# SparkFun_tDof-TMF8821_HQ.net
KiCad netlist of a schematic drawn in EAGLE
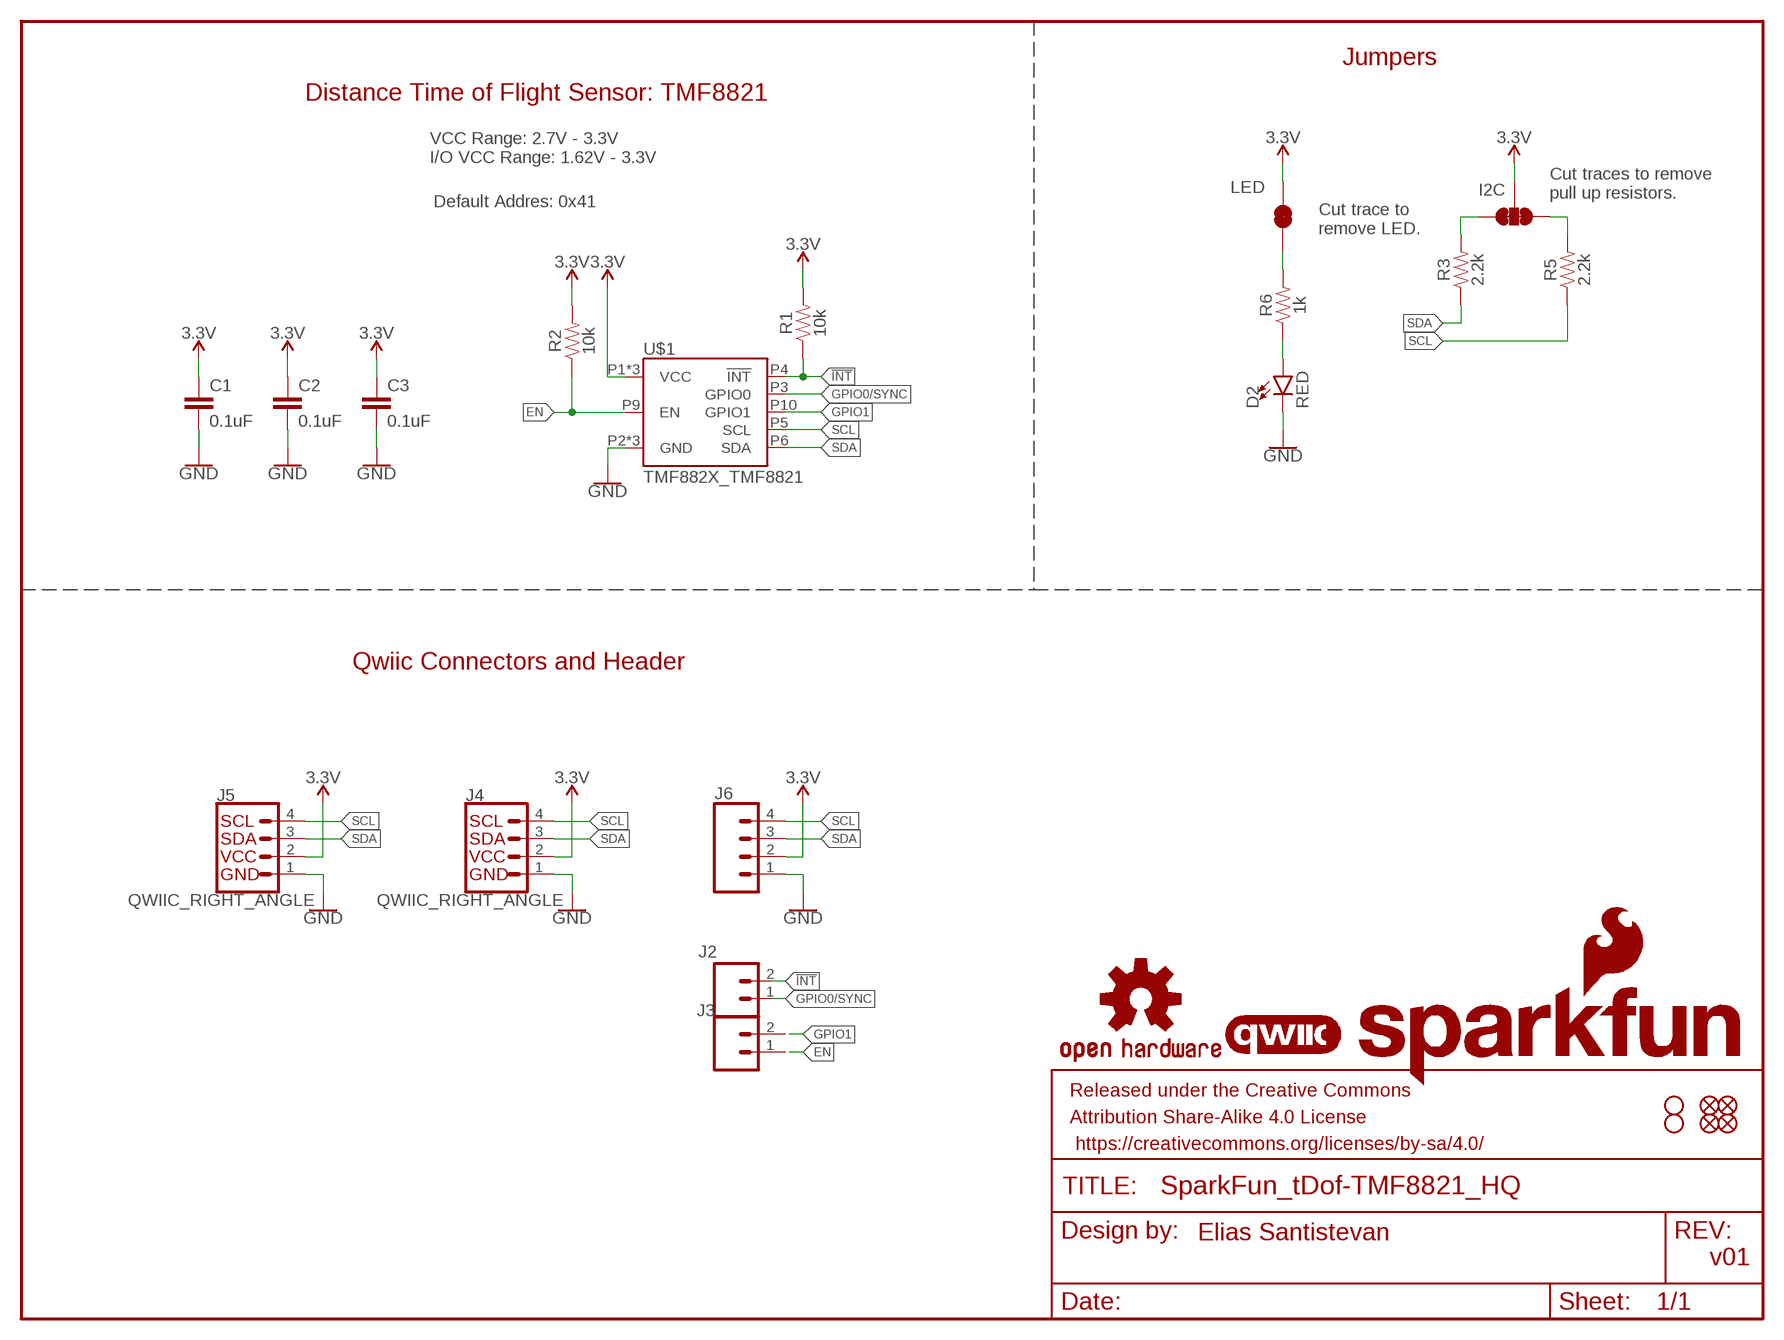
[diagram p0: schematic, sheet 1]

(export (version "E")
  (design (tool "Eeschema 10.0.6"))
  (components
    (comp (ref "C1")
      (value "0.1uF")
      (footprint "eagle-import:0402-TIGHT")
      (libsource (lib "eagle-import") (part "0.1UF-0402T-6.3V-10%-X7R"))
    )
    (comp (ref "C2")
      (value "0.1uF")
      (footprint "eagle-import:0402-TIGHT")
      (libsource (lib "eagle-import") (part "0.1UF-0402T-6.3V-10%-X7R"))
    )
    (comp (ref "C3")
      (value "0.1uF")
      (footprint "eagle-import:0402-TIGHT")
      (libsource (lib "eagle-import") (part "0.1UF-0402T-6.3V-10%-X7R"))
    )
    (comp (ref "D2")
      (value "RED")
      (footprint "eagle-import:LED-0603")
      (libsource (lib "eagle-import") (part "LED-RED0603"))
    )
    (comp (ref "FD5")
      (value "FIDUCIALUFIDUCIAL")
      (footprint "eagle-import:FIDUCIAL-MICRO")
      (libsource (lib "eagle-import") (part "FIDUCIALUFIDUCIAL"))
    )
    (comp (ref "FD6")
      (value "FIDUCIALUFIDUCIAL")
      (footprint "eagle-import:FIDUCIAL-MICRO")
      (libsource (lib "eagle-import") (part "FIDUCIALUFIDUCIAL"))
    )
    (comp (ref "FD7")
      (value "FIDUCIALUFIDUCIAL")
      (footprint "eagle-import:FIDUCIAL-MICRO")
      (libsource (lib "eagle-import") (part "FIDUCIALUFIDUCIAL"))
    )
    (comp (ref "FD8")
      (value "FIDUCIALUFIDUCIAL")
      (footprint "eagle-import:FIDUCIAL-MICRO")
      (libsource (lib "eagle-import") (part "FIDUCIALUFIDUCIAL"))
    )
    (comp (ref "FRAME2")
      (value "FRAME-LETTER")
      (footprint "eagle-import:CREATIVE_COMMONS")
      (libsource (lib "eagle-import") (part "FRAME-LETTER"))
    )
    (comp (ref "H7")
      (value "STAND-OFFTIGHT")
      (footprint "eagle-import:STAND-OFF-TIGHT")
      (libsource (lib "eagle-import") (part "STAND-OFFTIGHT"))
    )
    (comp (ref "H8")
      (value "STAND-OFFTIGHT")
      (footprint "eagle-import:STAND-OFF-TIGHT")
      (libsource (lib "eagle-import") (part "STAND-OFFTIGHT"))
    )
    (comp (ref "I2C")
      (value "I2C_PU")
      (footprint "eagle-import:SMT-JUMPER_3_2-NC_TRACE_SILK")
      (libsource (lib "eagle-import") (part "JUMPER-SMT_3_2-NC_TRACE_SILK"))
    )
    (comp (ref "J2")
      (value "CONN_021X02_NO_SILK")
      (footprint "eagle-import:1X02_NO_SILK")
      (libsource (lib "eagle-import") (part "CONN_021X02_NO_SILK"))
    )
    (comp (ref "J3")
      (value "CONN_021X02_NO_SILK")
      (footprint "eagle-import:1X02_NO_SILK")
      (libsource (lib "eagle-import") (part "CONN_021X02_NO_SILK"))
    )
    (comp (ref "J4")
      (value "QWIIC_RIGHT_ANGLE")
      (footprint "eagle-import:JST04_1MM_RA")
      (libsource (lib "eagle-import") (part "QWIIC_CONNECTORJS-1MM"))
    )
    (comp (ref "J5")
      (value "QWIIC_RIGHT_ANGLE")
      (footprint "eagle-import:JST04_1MM_RA")
      (libsource (lib "eagle-import") (part "QWIIC_CONNECTORJS-1MM"))
    )
    (comp (ref "J6")
      (value "CONN_041X04_NO_SILK")
      (footprint "eagle-import:1X04_NO_SILK")
      (libsource (lib "eagle-import") (part "CONN_041X04_NO_SILK"))
    )
    (comp (ref "LED")
      (value "LED")
      (footprint "eagle-import:SMT-JUMPER_2_NC_TRACE_SILK")
      (libsource (lib "eagle-import") (part "JUMPER-SMT_2_NC_TRACE_SILK"))
    )
    (comp (ref "LOGO1")
      (value "SFE_LOGO_NAME_FLAMEBLANK")
      (footprint "eagle-import:BLANK")
      (libsource (lib "eagle-import") (part "SFE_LOGO_NAME_FLAMEBLANK"))
    )
    (comp (ref "LOGO2")
      (value "QWIIC_LOGO_3MM")
      (footprint "eagle-import:QWIIC_3MM")
      (libsource (lib "eagle-import") (part "QWIIC_LOGO_3MM"))
    )
    (comp (ref "LOGO3")
      (value "OSHW-LOGONO_SILK")
      (footprint "eagle-import:DUMMY")
      (libsource (lib "eagle-import") (part "OSHW-LOGONO_SILK"))
    )
    (comp (ref "R1")
      (value "10k")
      (footprint "eagle-import:0402-TIGHT")
      (libsource (lib "eagle-import") (part "10KOHM-0402T-1/16W-1%"))
    )
    (comp (ref "R2")
      (value "10k")
      (footprint "eagle-import:0402-TIGHT")
      (libsource (lib "eagle-import") (part "10KOHM-0402T-1/16W-1%"))
    )
    (comp (ref "R3")
      (value "2.2k")
      (footprint "eagle-import:0402-TIGHT")
      (libsource (lib "eagle-import") (part "2.2KOHM-0402T-1/16W-1%"))
    )
    (comp (ref "R5")
      (value "2.2k")
      (footprint "eagle-import:0402-TIGHT")
      (libsource (lib "eagle-import") (part "2.2KOHM-0402T-1/16W-1%"))
    )
    (comp (ref "R6")
      (value "1k")
      (footprint "eagle-import:0402-TIGHT")
      (libsource (lib "eagle-import") (part "1KOHM-0402T-1/16W-1%"))
    )
    (comp (ref "U$1")
      (value "TMF882X_TMF8821")
      (footprint "eagle-import:TMF882X")
      (libsource (lib "eagle-import") (part "TMF882X_TMF8821"))
    )
  )
  (nets
    (net (code "1") (name "/~{INT}") (class "Default")
      (node (ref "J2") (pin "2") (pinfunction "2_2") (pintype "passive"))
      (node (ref "R1") (pin "1") (pinfunction "1_1") (pintype "passive"))
      (node (ref "U$1") (pin "P4") (pinfunction "~{INT}_P4") (pintype "bidirectional"))
    )
    (net (code "2") (name "3.3V") (class "Default")
      (node (ref "C1") (pin "1") (pinfunction "1_1") (pintype "passive"))
      (node (ref "C2") (pin "1") (pinfunction "1_1") (pintype "passive"))
      (node (ref "C3") (pin "1") (pinfunction "1_1") (pintype "passive"))
      (node (ref "I2C") (pin "2") (pinfunction "2_2") (pintype "passive"))
      (node (ref "J4") (pin "2") (pinfunction "2_2") (pintype "power_in"))
      (node (ref "J5") (pin "2") (pinfunction "2_2") (pintype "power_in"))
      (node (ref "J6") (pin "2") (pinfunction "2_2") (pintype "passive"))
      (node (ref "LED") (pin "2") (pinfunction "2_2") (pintype "passive"))
      (node (ref "R1") (pin "2") (pinfunction "2_2") (pintype "passive"))
      (node (ref "R2") (pin "2") (pinfunction "2_2") (pintype "passive"))
      (node (ref "U$1") (pin "P1") (pinfunction "VCC_P1") (pintype "power_in"))
      (node (ref "U$1") (pin "P12") (pinfunction "VCC_P12") (pintype "power_in"))
      (node (ref "U$1") (pin "P7") (pinfunction "VCC_P7") (pintype "power_in"))
    )
    (net (code "3") (name "EN") (class "Default")
      (node (ref "J3") (pin "1") (pinfunction "1_1") (pintype "passive"))
      (node (ref "R2") (pin "1") (pinfunction "1_1") (pintype "passive"))
      (node (ref "U$1") (pin "P9") (pinfunction "EN_P9") (pintype "input"))
    )
    (net (code "4") (name "GND") (class "Default")
      (node (ref "C1") (pin "2") (pinfunction "2_2") (pintype "passive"))
      (node (ref "C2") (pin "2") (pinfunction "2_2") (pintype "passive"))
      (node (ref "C3") (pin "2") (pinfunction "2_2") (pintype "passive"))
      (node (ref "D2") (pin "C") (pinfunction "C_C") (pintype "passive"))
      (node (ref "J4") (pin "1") (pinfunction "1_1") (pintype "power_in"))
      (node (ref "J5") (pin "1") (pinfunction "1_1") (pintype "power_in"))
      (node (ref "J6") (pin "1") (pinfunction "1_1") (pintype "passive"))
      (node (ref "U$1") (pin "P11") (pinfunction "GND_P11") (pintype "power_in"))
      (node (ref "U$1") (pin "P2") (pinfunction "GND_P2") (pintype "power_in"))
      (node (ref "U$1") (pin "P8") (pinfunction "GND_P8") (pintype "power_in"))
    )
    (net (code "5") (name "GPIO0{slash}SYNC") (class "Default")
      (node (ref "J2") (pin "1") (pinfunction "1_1") (pintype "passive"))
      (node (ref "U$1") (pin "P3") (pinfunction "GPIO0_P3") (pintype "bidirectional"))
    )
    (net (code "6") (name "GPIO1") (class "Default")
      (node (ref "J3") (pin "2") (pinfunction "2_2") (pintype "passive"))
      (node (ref "U$1") (pin "P10") (pinfunction "GPIO1_P10") (pintype "bidirectional"))
    )
    (net (code "7") (name "Net-(D2-PadA)") (class "Default")
      (node (ref "D2") (pin "A") (pinfunction "A_A") (pintype "passive"))
      (node (ref "R6") (pin "1") (pinfunction "1_1") (pintype "passive"))
    )
    (net (code "8") (name "Net-(I2C-Pad1)") (class "Default")
      (node (ref "I2C") (pin "1") (pinfunction "1_1") (pintype "passive"))
      (node (ref "R5") (pin "2") (pinfunction "2_2") (pintype "passive"))
    )
    (net (code "9") (name "Net-(I2C-Pad3)") (class "Default")
      (node (ref "I2C") (pin "3") (pinfunction "3_3") (pintype "passive"))
      (node (ref "R3") (pin "2") (pinfunction "2_2") (pintype "passive"))
    )
    (net (code "10") (name "Net-(LED-Pad1)") (class "Default")
      (node (ref "LED") (pin "1") (pinfunction "1_1") (pintype "passive"))
      (node (ref "R6") (pin "2") (pinfunction "2_2") (pintype "passive"))
    )
    (net (code "11") (name "SCL") (class "Default")
      (node (ref "J4") (pin "4") (pinfunction "4_4") (pintype "passive"))
      (node (ref "J5") (pin "4") (pinfunction "4_4") (pintype "passive"))
      (node (ref "J6") (pin "4") (pinfunction "4_4") (pintype "passive"))
      (node (ref "R5") (pin "1") (pinfunction "1_1") (pintype "passive"))
      (node (ref "U$1") (pin "P5") (pinfunction "SCL_P5") (pintype "bidirectional"))
    )
    (net (code "12") (name "SDA") (class "Default")
      (node (ref "J4") (pin "3") (pinfunction "3_3") (pintype "passive"))
      (node (ref "J5") (pin "3") (pinfunction "3_3") (pintype "passive"))
      (node (ref "J6") (pin "3") (pinfunction "3_3") (pintype "passive"))
      (node (ref "R3") (pin "1") (pinfunction "1_1") (pintype "passive"))
      (node (ref "U$1") (pin "P6") (pinfunction "SDA_P6") (pintype "bidirectional"))
    )
  )
)
